# XBee_v1.net
KiCad netlist of a schematic drawn in EAGLE
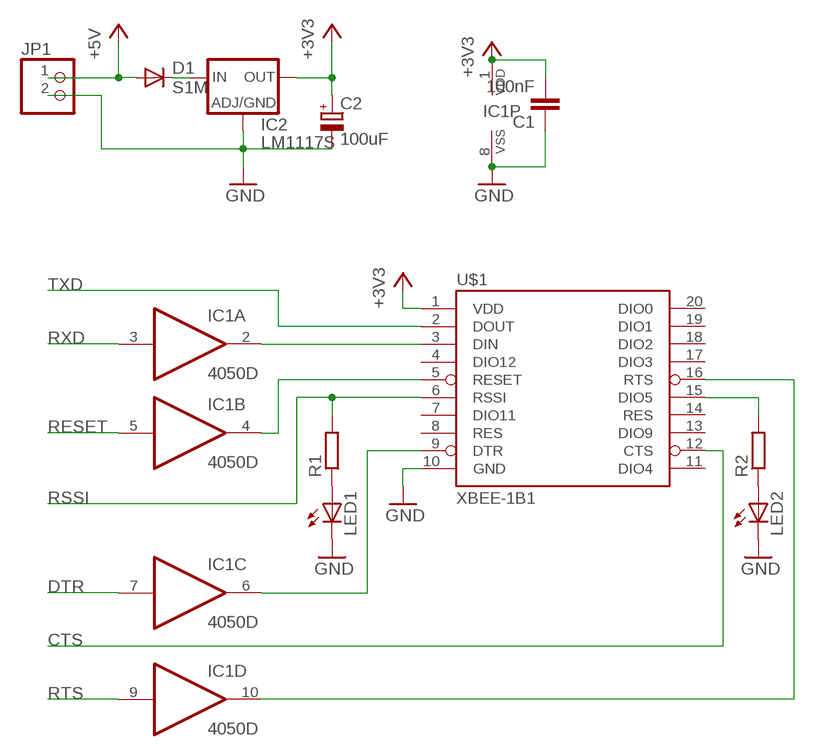
[diagram p0: schematic, sheet 1]

(export (version "E")
  (design (tool "Eeschema 10.0.6"))
  (components
    (comp (ref "C1")
      (value "100nF")
      (footprint "eagle-import:C0805K")
      (libsource (lib "eagle-import") (part "C-EUC0805K"))
    )
    (comp (ref "C2")
      (value "100uF")
      (footprint "eagle-import:PANASONIC_D")
      (libsource (lib "eagle-import") (part "CPOL-EUPD"))
    )
    (comp (ref "D1")
      (value "S1M")
      (footprint "eagle-import:DO-214AC")
      (libsource (lib "eagle-import") (part "S1M"))
    )
    (comp (ref "IC1")
      (value "4050D")
      (footprint "eagle-import:SO16")
      (libsource (lib "eagle-import") (part "4050D"))
    )
    (comp (ref "IC2")
      (value "LM1117S")
      (footprint "eagle-import:SOT223")
      (libsource (lib "eagle-import") (part "LM1117S"))
    )
    (comp (ref "JP1")
      (value "PINHD-1X2")
      (footprint "eagle-import:1X02")
      (libsource (lib "eagle-import") (part "PINHD-1X2"))
    )
    (comp (ref "LED1")
      (value "LED0805")
      (footprint "eagle-import:CHIP-LED0805")
      (libsource (lib "eagle-import") (part "LED0805"))
    )
    (comp (ref "LED2")
      (value "LED0805")
      (footprint "eagle-import:CHIP-LED0805")
      (libsource (lib "eagle-import") (part "LED0805"))
    )
    (comp (ref "R1")
      (value "R-EU_R0805")
      (footprint "eagle-import:R0805")
      (libsource (lib "eagle-import") (part "R-EU_R0805"))
    )
    (comp (ref "R2")
      (value "R-EU_R0805")
      (footprint "eagle-import:R0805")
      (libsource (lib "eagle-import") (part "R-EU_R0805"))
    )
    (comp (ref "U$1")
      (value "XBEE-1B1")
      (footprint "eagle-import:XBEE-1")
      (libsource (lib "eagle-import") (part "XBEE-1B1"))
    )
  )
  (nets
    (net (code "1") (name "+3V3") (class "Default")
      (node (ref "C1") (pin "2") (pinfunction "2_2") (pintype "passive"))
      (node (ref "C2") (pin "+") (pinfunction "+_+") (pintype "passive"))
      (node (ref "IC1") (pin "1") (pinfunction "VDD_1") (pintype "power_in"))
      (node (ref "IC2") (pin "2") (pinfunction "OUT_2") (pintype "passive"))
      (node (ref "IC2") (pin "4") (pinfunction "OUT_4") (pintype "passive"))
      (node (ref "U$1") (pin "1") (pinfunction "VDD_1") (pintype "power_in"))
    )
    (net (code "2") (name "+5V") (class "Default")
      (node (ref "D1") (pin "A") (pinfunction "A_A") (pintype "passive"))
      (node (ref "JP1") (pin "1") (pinfunction "1_1") (pintype "passive"))
    )
    (net (code "3") (name "/CTS") (class "Default")
      (node (ref "U$1") (pin "12") (pinfunction "CTS_12") (pintype "output"))
    )
    (net (code "4") (name "/DTR") (class "Default")
      (node (ref "IC1") (pin "7") (pinfunction "I_7") (pintype "input"))
    )
    (net (code "5") (name "/RESET") (class "Default")
      (node (ref "IC1") (pin "5") (pinfunction "I_5") (pintype "input"))
    )
    (net (code "6") (name "/RSSI") (class "Default")
      (node (ref "R1") (pin "2") (pinfunction "2_2") (pintype "passive"))
      (node (ref "U$1") (pin "6") (pinfunction "RSSI_6") (pintype "bidirectional"))
    )
    (net (code "7") (name "/RTS") (class "Default")
      (node (ref "IC1") (pin "9") (pinfunction "I_9") (pintype "input"))
    )
    (net (code "8") (name "/RXD") (class "Default")
      (node (ref "IC1") (pin "3") (pinfunction "I_3") (pintype "input"))
    )
    (net (code "9") (name "/TXD") (class "Default")
      (node (ref "U$1") (pin "2") (pinfunction "DOUT_2") (pintype "output"))
    )
    (net (code "10") (name "GND") (class "Default")
      (node (ref "C1") (pin "1") (pinfunction "1_1") (pintype "passive"))
      (node (ref "C2") (pin "-") (pinfunction "-_-") (pintype "passive"))
      (node (ref "IC1") (pin "8") (pinfunction "VSS_8") (pintype "power_in"))
      (node (ref "IC2") (pin "1") (pinfunction "ADJ_1") (pintype "input"))
      (node (ref "JP1") (pin "2") (pinfunction "2_2") (pintype "passive"))
      (node (ref "LED1") (pin "C") (pinfunction "C_C") (pintype "passive"))
      (node (ref "LED2") (pin "C") (pinfunction "C_C") (pintype "passive"))
      (node (ref "U$1") (pin "10") (pinfunction "GND_10") (pintype "power_in"))
    )
    (net (code "11") (name "Net-(IC1A-O)") (class "Default")
      (node (ref "IC1") (pin "2") (pinfunction "O_2") (pintype "output"))
      (node (ref "U$1") (pin "3") (pinfunction "DIN_3") (pintype "input"))
    )
    (net (code "12") (name "Net-(IC1B-O)") (class "Default")
      (node (ref "IC1") (pin "4") (pinfunction "O_4") (pintype "output"))
      (node (ref "U$1") (pin "5") (pinfunction "RESET_5") (pintype "input"))
    )
    (net (code "13") (name "Net-(IC1C-O)") (class "Default")
      (node (ref "IC1") (pin "6") (pinfunction "O_6") (pintype "output"))
      (node (ref "U$1") (pin "9") (pinfunction "DTR_9") (pintype "bidirectional"))
    )
    (net (code "14") (name "Net-(IC1D-O)") (class "Default")
      (node (ref "IC1") (pin "10") (pinfunction "O_10") (pintype "output"))
      (node (ref "U$1") (pin "16") (pinfunction "RTS_16") (pintype "input"))
    )
    (net (code "15") (name "Net-(IC2-IN)") (class "Default")
      (node (ref "D1") (pin "C") (pinfunction "C_C") (pintype "passive"))
      (node (ref "IC2") (pin "3") (pinfunction "IN_3") (pintype "input"))
    )
    (net (code "16") (name "Net-(LED1-PadA)") (class "Default")
      (node (ref "LED1") (pin "A") (pinfunction "A_A") (pintype "passive"))
      (node (ref "R1") (pin "1") (pinfunction "1_1") (pintype "passive"))
    )
    (net (code "17") (name "Net-(LED2-PadA)") (class "Default")
      (node (ref "LED2") (pin "A") (pinfunction "A_A") (pintype "passive"))
      (node (ref "R2") (pin "1") (pinfunction "1_1") (pintype "passive"))
    )
    (net (code "18") (name "Net-(U$1-DIO5)") (class "Default")
      (node (ref "R2") (pin "2") (pinfunction "2_2") (pintype "passive"))
      (node (ref "U$1") (pin "15") (pinfunction "DIO5_15") (pintype "bidirectional"))
    )
    (net (code "19") (name "unconnected-(U$1-DIO0-Pad20)") (class "Default")
      (node (ref "U$1") (pin "20") (pinfunction "DIO0_20") (pintype "bidirectional"))
    )
    (net (code "20") (name "unconnected-(U$1-DIO1-Pad19)") (class "Default")
      (node (ref "U$1") (pin "19") (pinfunction "DIO1_19") (pintype "bidirectional"))
    )
    (net (code "21") (name "unconnected-(U$1-DIO2-Pad18)") (class "Default")
      (node (ref "U$1") (pin "18") (pinfunction "DIO2_18") (pintype "bidirectional"))
    )
    (net (code "22") (name "unconnected-(U$1-DIO3-Pad17)") (class "Default")
      (node (ref "U$1") (pin "17") (pinfunction "DIO3_17") (pintype "bidirectional"))
    )
    (net (code "23") (name "unconnected-(U$1-DIO4-Pad11)") (class "Default")
      (node (ref "U$1") (pin "11") (pinfunction "DIO4_11") (pintype "bidirectional"))
    )
    (net (code "24") (name "unconnected-(U$1-DIO9-Pad13)") (class "Default")
      (node (ref "U$1") (pin "13") (pinfunction "DIO9_13") (pintype "bidirectional"))
    )
    (net (code "25") (name "unconnected-(U$1-DIO11-Pad7)") (class "Default")
      (node (ref "U$1") (pin "7") (pinfunction "DIO11_7") (pintype "bidirectional"))
    )
    (net (code "26") (name "unconnected-(U$1-DIO12-Pad4)") (class "Default")
      (node (ref "U$1") (pin "4") (pinfunction "DIO12_4") (pintype "bidirectional"))
    )
    (net (code "27") (name "unconnected-(U$1-RES-Pad8)") (class "Default")
      (node (ref "U$1") (pin "8") (pinfunction "RES_8") (pintype "bidirectional"))
    )
    (net (code "28") (name "unconnected-(U$1-RES-Pad14)") (class "Default")
      (node (ref "U$1") (pin "14") (pinfunction "RES_14") (pintype "bidirectional"))
    )
  )
)
